# Sheet1.net
KiCad netlist of a schematic drawn in Altium Designer
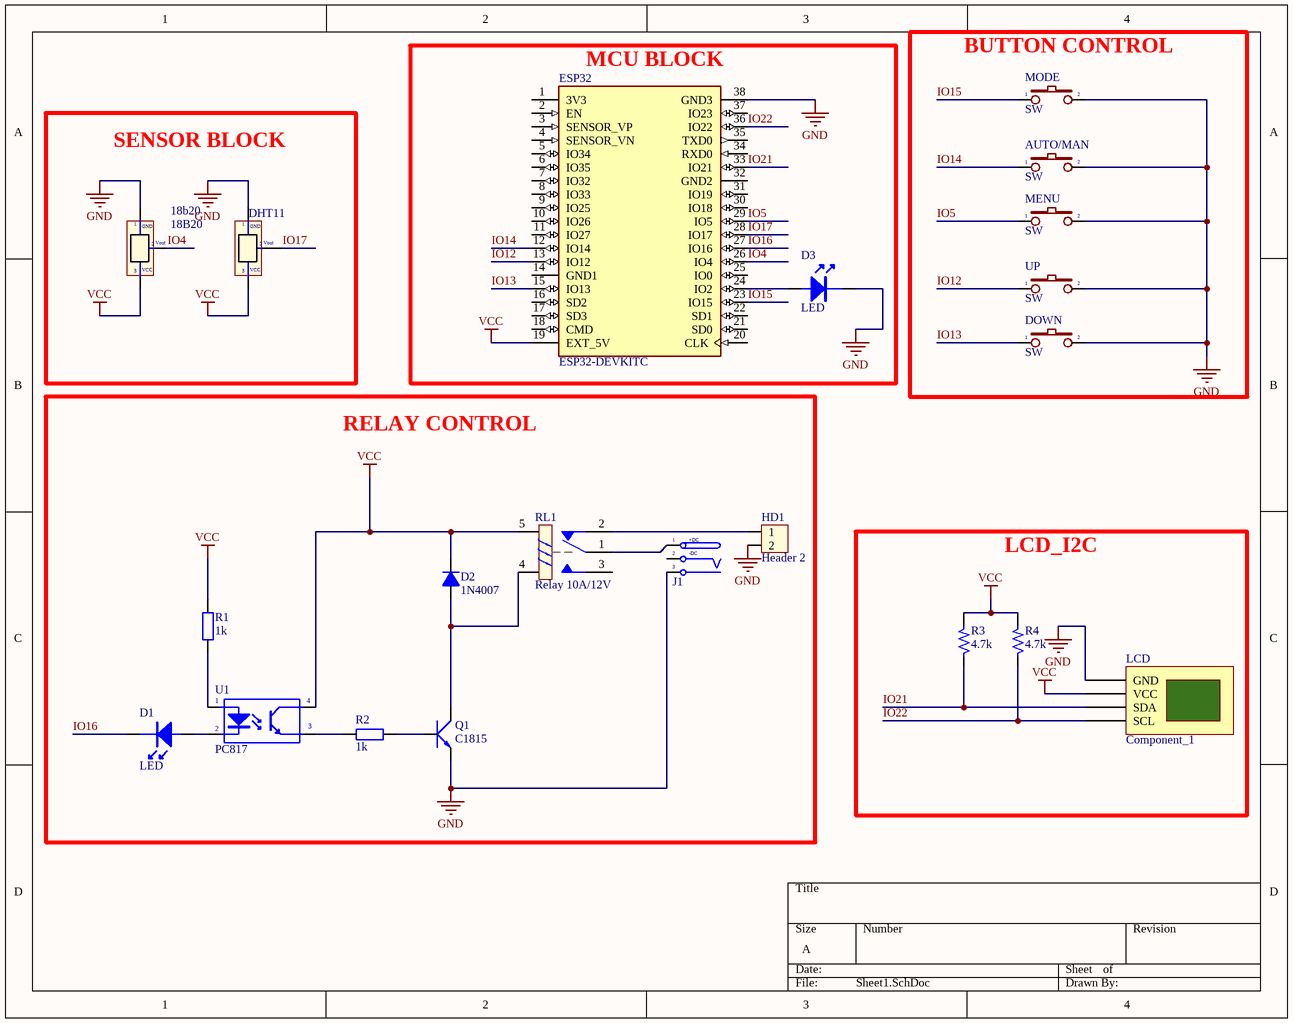
[diagram p0: Sheet1.SchDoc]

(export (version "E")
  (design (tool "Eeschema 10.0.6"))
  (components
    (comp (ref "18b20") (value "18B20") (footprint "HED3") (libsource (lib "Cty1") (part "18B20")))
    (comp (ref "AUTO/MAN")
      (value "SW")
      (footprint "SW2")
      (description "Switch button 2 pin")
      (libsource (lib "Cty1") (part "SW2"))
    )
    (comp (ref "D1") (value "LED") (footprint "CAP10UF") (libsource (lib "Cty1") (part "LED")))
    (comp (ref "D2")
      (value "1N4007")
      (footprint "D1A")
      (description "Diode 1A")
      (libsource (lib "Cty1") (part "D1A"))
    )
    (comp (ref "D3") (value "LED") (footprint "CAP10UF") (libsource (lib "Cty1") (part "LED")))
    (comp (ref "DHT11")
      (value "Component_1")
      (footprint "Jumper 3")
      (libsource (lib "DHT11") (part "Component_1"))
    )
    (comp (ref "DOWN")
      (value "SW")
      (footprint "SW2")
      (description "Switch button 2 pin")
      (libsource (lib "Cty1") (part "SW2"))
    )
    (comp (ref "ESP32")
      (value "ESP32-DEVKITC")
      (footprint "MODULE_ESP32-DEVKITC")
      (fields (field (name "MF") "Espressif Systems"))
      (libsource (lib "ESP32-DEVKITC") (part "ESP32-DEVKITC"))
    )
    (comp (ref "HD1")
      (value "Header 2")
      (footprint "HED2")
      (description "Header 2 (Green)")
      (libsource (lib "Cty1") (part "Hed2"))
    )
    (comp (ref "J1")
      (value "JACK DC 5MM")
      (footprint "JACK DC 5MM")
      (libsource (lib "Cty1") (part "JACK DC 5MM"))
    )
    (comp (ref "LCD")
      (value "Component_1")
      (footprint "Jumper 4")
      (libsource (lib "Schlib1") (part "Component_1"))
    )
    (comp (ref "MENU")
      (value "SW")
      (footprint "SW2")
      (description "Switch button 2 pin")
      (libsource (lib "Cty1") (part "SW2"))
    )
    (comp (ref "MODE")
      (value "SW")
      (footprint "SW2")
      (description "Switch button 2 pin")
      (libsource (lib "Cty1") (part "SW2"))
    )
    (comp (ref "Q1")
      (value "C1815")
      (footprint "TO126")
      (description "NPN 600mW, ECB")
      (libsource (lib "Cty1") (part "C1815"))
    )
    (comp (ref "R1")
      (value "1k")
      (footprint "R1/4W")
      (description "Resistor 1/4W")
      (libsource (lib "Cty1") (part "R1/4W"))
    )
    (comp (ref "R2")
      (value "1k")
      (footprint "R1/4W")
      (description "Resistor 1/4W")
      (libsource (lib "Cty1") (part "R1/4W"))
    )
    (comp (ref "R3")
      (value "4.7k")
      (footprint "R1/6W")
      (description "Resistor 1/4W")
      (libsource (lib "Cty1") (part "Res"))
    )
    (comp (ref "R4")
      (value "4.7k")
      (footprint "R1/6W")
      (description "Resistor 1/4W")
      (libsource (lib "Cty1") (part "Res"))
    )
    (comp (ref "RL1")
      (value "Relay 10A/12V")
      (footprint "RL_SPDT_10A")
      (description "Relay SPDT,10A - 12VDC 5 Pin")
      (libsource (lib "Cty1") (part "Relay 1"))
    )
    (comp (ref "U1")
      (value "PC817")
      (footprint "DIP4/W0.3")
      (description "Single Opto")
      (libsource (lib "Cty1") (part "PC817_1"))
    )
    (comp (ref "UP")
      (value "SW")
      (footprint "SW2")
      (description "Switch button 2 pin")
      (libsource (lib "Cty1") (part "SW2"))
    )
  )
  (nets
    (net (code "1") (name "/IO4") (class "Default")
      (node (ref "18b20") (pin "2") (pinfunction "Vout_2") (pintype "passive"))
      (node (ref "ESP32") (pin "26") (pinfunction "IO4_26") (pintype "bidirectional"))
    )
    (net (code "2") (name "/IO5") (class "Default")
      (node (ref "ESP32") (pin "29") (pinfunction "IO5_29") (pintype "bidirectional"))
      (node (ref "MENU") (pin "1") (pinfunction "1_1") (pintype "passive"))
    )
    (net (code "3") (name "/IO12") (class "Default")
      (node (ref "ESP32") (pin "13") (pinfunction "IO12_13") (pintype "bidirectional"))
      (node (ref "UP") (pin "1") (pinfunction "1_1") (pintype "passive"))
    )
    (net (code "4") (name "/IO13") (class "Default")
      (node (ref "DOWN") (pin "1") (pinfunction "1_1") (pintype "passive"))
      (node (ref "ESP32") (pin "15") (pinfunction "IO13_15") (pintype "bidirectional"))
    )
    (net (code "5") (name "/IO14") (class "Default")
      (node (ref "AUTO/MAN") (pin "1") (pinfunction "1_1") (pintype "passive"))
      (node (ref "ESP32") (pin "12") (pinfunction "IO14_12") (pintype "bidirectional"))
    )
    (net (code "6") (name "/IO15") (class "Default")
      (node (ref "ESP32") (pin "23") (pinfunction "IO15_23") (pintype "bidirectional"))
      (node (ref "MODE") (pin "1") (pinfunction "1_1") (pintype "passive"))
    )
    (net (code "7") (name "/IO16") (class "Default")
      (node (ref "D1") (pin "2") (pinfunction "2_2") (pintype "passive"))
      (node (ref "ESP32") (pin "27") (pinfunction "IO16_27") (pintype "bidirectional"))
    )
    (net (code "8") (name "/IO17") (class "Default")
      (node (ref "DHT11") (pin "2") (pinfunction "Vout_2") (pintype "passive"))
      (node (ref "ESP32") (pin "28") (pinfunction "IO17_28") (pintype "bidirectional"))
    )
    (net (code "9") (name "/IO21") (class "Default")
      (node (ref "ESP32") (pin "33") (pinfunction "IO21_33") (pintype "bidirectional"))
      (node (ref "LCD") (pin "3") (pinfunction "SDA_3") (pintype "passive"))
      (node (ref "R3") (pin "1") (pinfunction "1_1") (pintype "passive"))
    )
    (net (code "10") (name "/IO22") (class "Default")
      (node (ref "ESP32") (pin "36") (pinfunction "IO22_36") (pintype "bidirectional"))
      (node (ref "LCD") (pin "4") (pinfunction "SCL_4") (pintype "passive"))
      (node (ref "R4") (pin "1") (pinfunction "1_1") (pintype "passive"))
    )
    (net (code "11") (name "GND") (class "Default")
      (node (ref "18b20") (pin "1") (pinfunction "GND_1") (pintype "power_in"))
      (node (ref "AUTO/MAN") (pin "2") (pinfunction "2_2") (pintype "passive"))
      (node (ref "D3") (pin "2") (pinfunction "2_2") (pintype "passive"))
      (node (ref "DHT11") (pin "1") (pinfunction "GND_1") (pintype "power_in"))
      (node (ref "DOWN") (pin "2") (pinfunction "2_2") (pintype "passive"))
      (node (ref "ESP32") (pin "38") (pinfunction "GND3_38") (pintype "power_in"))
      (node (ref "HD1") (pin "2") (pinfunction "2_2") (pintype "passive"))
      (node (ref "J1") (pin "3") (pinfunction "S_3") (pintype "power_in"))
      (node (ref "LCD") (pin "1") (pinfunction "GND_1") (pintype "passive"))
      (node (ref "MENU") (pin "2") (pinfunction "2_2") (pintype "passive"))
      (node (ref "MODE") (pin "2") (pinfunction "2_2") (pintype "passive"))
      (node (ref "Q1") (pin "3") (pinfunction "E_3") (pintype "passive"))
      (node (ref "UP") (pin "2") (pinfunction "2_2") (pintype "passive"))
    )
    (net (code "12") (name "Net-(D2-A)") (class "Default")
      (node (ref "D2") (pin "1") (pinfunction "A_1") (pintype "passive"))
      (node (ref "Q1") (pin "2") (pinfunction "C_2") (pintype "passive"))
      (node (ref "RL1") (pin "4") (pinfunction "4_4") (pintype "passive"))
    )
    (net (code "13") (name "Net-(ESP32-IO2)") (class "Default")
      (node (ref "D3") (pin "1") (pinfunction "1_1") (pintype "passive"))
      (node (ref "ESP32") (pin "24") (pinfunction "IO2_24") (pintype "bidirectional"))
    )
    (net (code "14") (name "Net-(HD1-Pad1)") (class "Default")
      (node (ref "HD1") (pin "1") (pinfunction "1_1") (pintype "passive"))
      (node (ref "RL1") (pin "2") (pinfunction "2_2") (pintype "passive"))
    )
    (net (code "15") (name "Net-(J1-T)") (class "Default")
      (node (ref "J1") (pin "1") (pinfunction "T_1") (pintype "passive"))
      (node (ref "RL1") (pin "1") (pinfunction "1_1") (pintype "passive"))
    )
    (net (code "16") (name "Net-(Q1-B)") (class "Default")
      (node (ref "Q1") (pin "1") (pinfunction "B_1") (pintype "passive"))
      (node (ref "R2") (pin "2") (pinfunction "2_2") (pintype "passive"))
    )
    (net (code "17") (name "Net-(U1-A)") (class "Default")
      (node (ref "R1") (pin "2") (pinfunction "2_2") (pintype "passive"))
      (node (ref "U1") (pin "1") (pinfunction "A_1") (pintype "passive"))
    )
    (net (code "18") (name "Net-(U1-E)") (class "Default")
      (node (ref "R2") (pin "1") (pinfunction "1_1") (pintype "passive"))
      (node (ref "U1") (pin "3") (pinfunction "E_3") (pintype "passive"))
    )
    (net (code "19") (name "Net-(U1-K)") (class "Default")
      (node (ref "D1") (pin "1") (pinfunction "1_1") (pintype "passive"))
      (node (ref "U1") (pin "2") (pinfunction "K_2") (pintype "passive"))
    )
    (net (code "20") (name "VCC") (class "Default")
      (node (ref "18b20") (pin "3") (pinfunction "V+_3") (pintype "power_in"))
      (node (ref "D2") (pin "2") (pinfunction "K_2") (pintype "passive"))
      (node (ref "DHT11") (pin "3") (pinfunction "V+_3") (pintype "power_in"))
      (node (ref "ESP32") (pin "19") (pinfunction "EXT_5V_19") (pintype "power_in"))
      (node (ref "LCD") (pin "2") (pinfunction "VCC_2") (pintype "passive"))
      (node (ref "R1") (pin "1") (pinfunction "1_1") (pintype "passive"))
      (node (ref "R3") (pin "2") (pinfunction "2_2") (pintype "passive"))
      (node (ref "R4") (pin "2") (pinfunction "2_2") (pintype "passive"))
      (node (ref "RL1") (pin "5") (pinfunction "5_5") (pintype "passive"))
      (node (ref "U1") (pin "4") (pinfunction "C_4") (pintype "passive"))
    )
    (net (code "21") (name "unconnected-(ESP32-3V3-Pad1)") (class "Default")
      (node (ref "ESP32") (pin "1") (pinfunction "3V3_1") (pintype "power_in"))
    )
    (net (code "22") (name "unconnected-(ESP32-CLK-Pad20)") (class "Default")
      (node (ref "ESP32") (pin "20") (pinfunction "CLK_20") (pintype "input"))
    )
    (net (code "23") (name "unconnected-(ESP32-CMD-Pad18)") (class "Default")
      (node (ref "ESP32") (pin "18") (pinfunction "CMD_18") (pintype "bidirectional"))
    )
    (net (code "24") (name "unconnected-(ESP32-EN-Pad2)") (class "Default")
      (node (ref "ESP32") (pin "2") (pinfunction "EN_2") (pintype "input"))
    )
    (net (code "25") (name "unconnected-(ESP32-GND1-Pad14)") (class "Default")
      (node (ref "ESP32") (pin "14") (pinfunction "GND1_14") (pintype "power_in"))
    )
    (net (code "26") (name "unconnected-(ESP32-GND2-Pad32)") (class "Default")
      (node (ref "ESP32") (pin "32") (pinfunction "GND2_32") (pintype "power_in"))
    )
    (net (code "27") (name "unconnected-(ESP32-IO0-Pad25)") (class "Default")
      (node (ref "ESP32") (pin "25") (pinfunction "IO0_25") (pintype "bidirectional"))
    )
    (net (code "28") (name "unconnected-(ESP32-IO18-Pad30)") (class "Default")
      (node (ref "ESP32") (pin "30") (pinfunction "IO18_30") (pintype "bidirectional"))
    )
    (net (code "29") (name "unconnected-(ESP32-IO19-Pad31)") (class "Default")
      (node (ref "ESP32") (pin "31") (pinfunction "IO19_31") (pintype "bidirectional"))
    )
    (net (code "30") (name "unconnected-(ESP32-IO23-Pad37)") (class "Default")
      (node (ref "ESP32") (pin "37") (pinfunction "IO23_37") (pintype "bidirectional"))
    )
    (net (code "31") (name "unconnected-(ESP32-IO25-Pad9)") (class "Default")
      (node (ref "ESP32") (pin "9") (pinfunction "IO25_9") (pintype "bidirectional"))
    )
    (net (code "32") (name "unconnected-(ESP32-IO26-Pad10)") (class "Default")
      (node (ref "ESP32") (pin "10") (pinfunction "IO26_10") (pintype "bidirectional"))
    )
    (net (code "33") (name "unconnected-(ESP32-IO27-Pad11)") (class "Default")
      (node (ref "ESP32") (pin "11") (pinfunction "IO27_11") (pintype "bidirectional"))
    )
    (net (code "34") (name "unconnected-(ESP32-IO32-Pad7)") (class "Default")
      (node (ref "ESP32") (pin "7") (pinfunction "IO32_7") (pintype "bidirectional"))
    )
    (net (code "35") (name "unconnected-(ESP32-IO33-Pad8)") (class "Default")
      (node (ref "ESP32") (pin "8") (pinfunction "IO33_8") (pintype "bidirectional"))
    )
    (net (code "36") (name "unconnected-(ESP32-IO34-Pad5)") (class "Default")
      (node (ref "ESP32") (pin "5") (pinfunction "IO34_5") (pintype "bidirectional"))
    )
    (net (code "37") (name "unconnected-(ESP32-IO35-Pad6)") (class "Default")
      (node (ref "ESP32") (pin "6") (pinfunction "IO35_6") (pintype "bidirectional"))
    )
    (net (code "38") (name "unconnected-(ESP32-RXD0-Pad34)") (class "Default")
      (node (ref "ESP32") (pin "34") (pinfunction "RXD0_34") (pintype "input"))
    )
    (net (code "39") (name "unconnected-(ESP32-SD0-Pad21)") (class "Default")
      (node (ref "ESP32") (pin "21") (pinfunction "SD0_21") (pintype "bidirectional"))
    )
    (net (code "40") (name "unconnected-(ESP32-SD1-Pad22)") (class "Default")
      (node (ref "ESP32") (pin "22") (pinfunction "SD1_22") (pintype "bidirectional"))
    )
    (net (code "41") (name "unconnected-(ESP32-SD2-Pad16)") (class "Default")
      (node (ref "ESP32") (pin "16") (pinfunction "SD2_16") (pintype "bidirectional"))
    )
    (net (code "42") (name "unconnected-(ESP32-SD3-Pad17)") (class "Default")
      (node (ref "ESP32") (pin "17") (pinfunction "SD3_17") (pintype "bidirectional"))
    )
    (net (code "43") (name "unconnected-(ESP32-SENSOR_VN-Pad4)") (class "Default")
      (node (ref "ESP32") (pin "4") (pinfunction "SENSOR_VN_4") (pintype "input"))
    )
    (net (code "44") (name "unconnected-(ESP32-SENSOR_VP-Pad3)") (class "Default")
      (node (ref "ESP32") (pin "3") (pinfunction "SENSOR_VP_3") (pintype "input"))
    )
    (net (code "45") (name "unconnected-(ESP32-TXD0-Pad35)") (class "Default")
      (node (ref "ESP32") (pin "35") (pinfunction "TXD0_35") (pintype "output"))
    )
    (net (code "46") (name "unconnected-(J1-TN-Pad2)") (class "Default")
      (node (ref "J1") (pin "2") (pinfunction "TN_2") (pintype "passive"))
    )
    (net (code "47") (name "unconnected-(RL1-Pad3)") (class "Default")
      (node (ref "RL1") (pin "3") (pinfunction "3_3") (pintype "passive"))
    )
  )
)
